# SY8003ADFC_4.net
KiCad netlist of a schematic drawn in Altium Designer
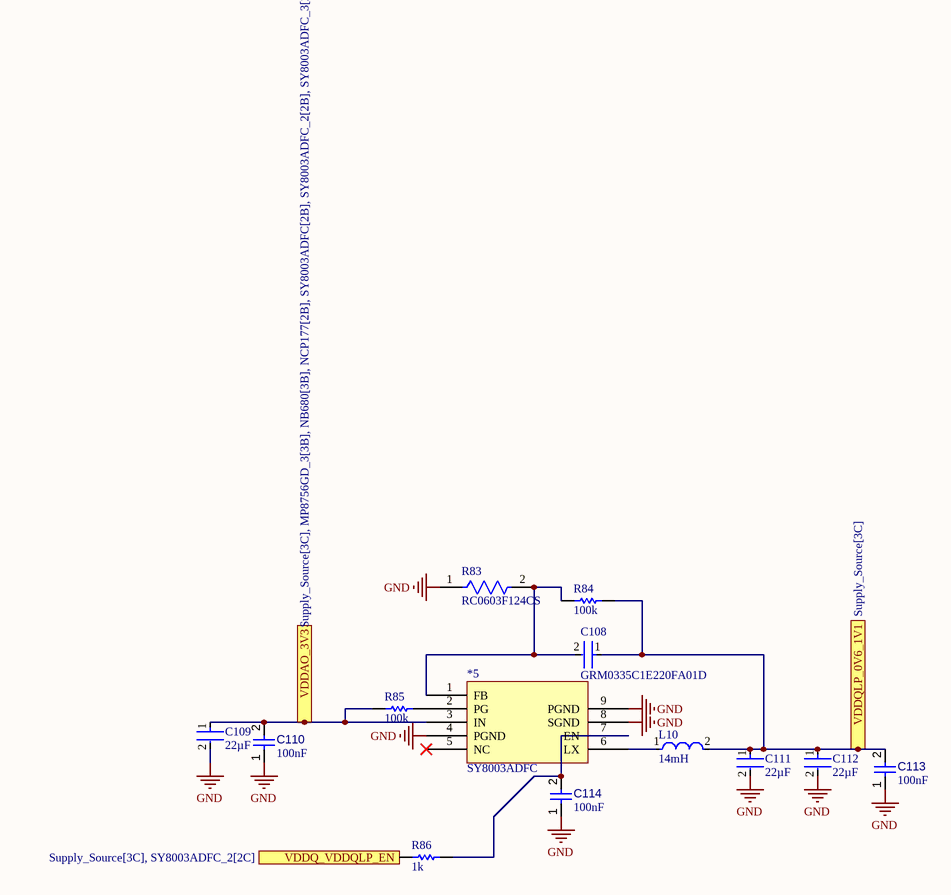
[diagram p0: SY8003ADFC_4.SchDoc]

(export (version "E")
  (design (tool "Eeschema 10.0.6"))
  (components
    (comp (ref "*5")
      (value "SY8003ADFC")
      (footprint "SON127P750X265-8N")
      (description "Switching Regulator, 3A, 1200kHz Switching Freq-Max, PDSO8")
      (libsource (lib "MIGUEL ANGEL ALVAREZ GUZMAN") (part "SY8003ADFC-Symbol-1"))
    )
    (comp (ref "C108")
      (value "GRM0335C1E220FA01D")
      (footprint "FP-GRM033-0_03-IPC_C")
      (description "Chip Multilayer Ceramic Capacitors for General Purpose, 0201, 22pF, C0G, 30ppm/°C, 1%, 25V")
      (fields (field (name "TOLERANCE") "1%"))
      (libsource (lib "Altium Content Vault") (part "b4654b650e69147ec39a6b967a45e02"))
    )
    (comp (ref "C109")
      (value "22µF")
      (footprint "FP-GRM186-0_2-IPC_A")
      (description "6.3V 22uF X5R ±20% 0603 Multilayer Ceramic Capacitors MLCC - SMD/SMT ROHS")
      (fields (field (name "TOLERANCE") "20%") (field (name "Comment") "GRM186R60J226ME15D"))
      (libsource (lib "MIGUEL ANGEL ALVAREZ GUZMAN") (part "02cd4be3c70576c341d710602a673aa"))
    )
    (comp (ref "C110")
      (value "100nF")
      (footprint "CAPC1005X56X25LL10T15")
      (description "Chip Capacitor, 0.1 uF, +/- 5%, 16 V, 0402 (1005 Metric)")
      (fields (field (name "TOLERANCE") "5%") (field (name "Comment") "Capacitor 0.1 uF +/- 5% 16 V 0402"))
      (libsource (lib "MIGUEL ANGEL ALVAREZ GUZMAN") (part "CAP-NP-2"))
    )
    (comp (ref "C111")
      (value "22µF")
      (footprint "FP-GRM186-0_2-IPC_A")
      (description "6.3V 22uF X5R ±20% 0603 Multilayer Ceramic Capacitors MLCC - SMD/SMT ROHS")
      (fields (field (name "TOLERANCE") "20%") (field (name "Comment") "GRM186R60J226ME15D"))
      (libsource (lib "MIGUEL ANGEL ALVAREZ GUZMAN") (part "02cd4be3c70576c341d710602a673aa"))
    )
    (comp (ref "C112")
      (value "22µF")
      (footprint "FP-GRM186-0_2-IPC_A")
      (description "6.3V 22uF X5R ±20% 0603 Multilayer Ceramic Capacitors MLCC - SMD/SMT ROHS")
      (fields (field (name "TOLERANCE") "20%") (field (name "Comment") "GRM186R60J226ME15D"))
      (libsource (lib "MIGUEL ANGEL ALVAREZ GUZMAN") (part "02cd4be3c70576c341d710602a673aa"))
    )
    (comp (ref "C113")
      (value "100nF")
      (footprint "CAPC1005X56X25LL10T15")
      (description "Chip Capacitor, 0.1 uF, +/- 5%, 16 V, 0402 (1005 Metric)")
      (fields (field (name "TOLERANCE") "5%") (field (name "Comment") "Capacitor 0.1 uF +/- 5% 16 V 0402"))
      (libsource (lib "MIGUEL ANGEL ALVAREZ GUZMAN") (part "CAP-NP-2"))
    )
    (comp (ref "C114")
      (value "100nF")
      (footprint "CAPC1005X56X25LL10T15")
      (description "Chip Capacitor, 0.1 uF, +/- 5%, 16 V, 0402 (1005 Metric)")
      (fields (field (name "TOLERANCE") "5%") (field (name "Comment") "Capacitor 0.1 uF +/- 5% 16 V 0402"))
      (libsource (lib "MIGUEL ANGEL ALVAREZ GUZMAN") (part "CAP-NP-2"))
    )
    (comp (ref "L10")
      (value "14mH")
      (footprint "FP-IHLP-2525CZ-FP_2_413x3-MFG")
      (description "Inductor High Current Shielded Wirewound 1.5uH 20% 100KHz 9A 15mOhm DCR 2525 T/R")
      (fields (field (name "TOLERANCE") "20%") (field (name "Comment") "IHLP2525CZER1R5M01"))
      (libsource (lib "MIGUEL ANGEL ALVAREZ GUZMAN") (part "725321dda6339637d4d059423bc1c3c"))
    )
    (comp (ref "R83")
      (value "RC0603F124CS")
      (footprint "FP-RC0603-MFG")
      (description "Res Thick Film 0201 120kΩ 1% 0.05W ±250ppm/°C Molded SMD T/R")
      (fields (field (name "TOLERANCE") "1%"))
      (libsource (lib "Altium Content Vault") (part "1029c3af85768c4190bb7ad29bc67b5"))
    )
    (comp (ref "R84")
      (value "100k")
      (footprint "RESC0603X26X15NL03T05")
      (description "Res General Purpose Thick Film 0201 100k Ohm 1% 1/20W ±200ppm/°C Molded Paper T/R")
      (fields (field (name "TOLERANCE") "1%") (field (name "Comment") "CRG0201F100K"))
      (libsource (lib "MIGUEL ANGEL ALVAREZ GUZMAN") (part "RES"))
    )
    (comp (ref "R85")
      (value "100k")
      (footprint "RESC0603X26X15NL03T05")
      (description "Res General Purpose Thick Film 0201 100k Ohm 1% 1/20W ±200ppm/°C Molded Paper T/R")
      (fields (field (name "TOLERANCE") "1%") (field (name "Comment") "CRG0201F100K"))
      (libsource (lib "MIGUEL ANGEL ALVAREZ GUZMAN") (part "RES"))
    )
    (comp (ref "R86")
      (value "1k")
      (footprint "RESC0603X26X15NL03T05")
      (description "Res General Purpose Thick Film 0201 1k Ohm 1% 1/20W ±200ppm/°C Molded Paper T/R")
      (fields (field (name "TOLERANCE") "1%") (field (name "Comment") "MCRE000140"))
      (libsource (lib "MIGUEL ANGEL ALVAREZ GUZMAN") (part "RES"))
    )
  )
  (nets
    (net (code "1") (name "/VDDAO_3V3") (class "Default")
      (node (ref "*5") (pin "3") (pinfunction "IN_3") (pintype "passive"))
      (node (ref "C109") (pin "1") (pinfunction "1_1") (pintype "passive"))
      (node (ref "C110") (pin "2") (pinfunction "2_2") (pintype "passive"))
      (node (ref "R85") (pin "1") (pinfunction "1_1") (pintype "passive"))
    )
    (net (code "2") (name "/VDDQLP_0V6_1V1") (class "Default")
      (node (ref "C108") (pin "1") (pinfunction "1_1") (pintype "passive"))
      (node (ref "C111") (pin "1") (pinfunction "1_1") (pintype "passive"))
      (node (ref "C112") (pin "1") (pinfunction "1_1") (pintype "passive"))
      (node (ref "C113") (pin "2") (pinfunction "2_2") (pintype "passive"))
      (node (ref "L10") (pin "2") (pinfunction "2_2") (pintype "passive"))
      (node (ref "R84") (pin "2") (pinfunction "2_2") (pintype "passive"))
    )
    (net (code "3") (name "/VDDQ_VDDQLP_EN") (class "Default")
      (node (ref "R86") (pin "1") (pinfunction "1_1") (pintype "passive"))
    )
    (net (code "4") (name "GND") (class "Default")
      (node (ref "*5") (pin "4") (pinfunction "PGND_4") (pintype "passive"))
      (node (ref "*5") (pin "8") (pinfunction "SGND_8") (pintype "passive"))
      (node (ref "*5") (pin "9") (pinfunction "PGND_9") (pintype "passive"))
      (node (ref "C109") (pin "2") (pinfunction "2_2") (pintype "passive"))
      (node (ref "C110") (pin "1") (pinfunction "1_1") (pintype "passive"))
      (node (ref "C111") (pin "2") (pinfunction "2_2") (pintype "passive"))
      (node (ref "C112") (pin "2") (pinfunction "2_2") (pintype "passive"))
      (node (ref "C113") (pin "1") (pinfunction "1_1") (pintype "passive"))
      (node (ref "C114") (pin "1") (pinfunction "1_1") (pintype "passive"))
      (node (ref "R83") (pin "1") (pinfunction "1_1") (pintype "passive"))
    )
    (net (code "5") (name "Net-(*5-EN)") (class "Default")
      (node (ref "*5") (pin "7") (pinfunction "EN_7") (pintype "passive"))
      (node (ref "C114") (pin "2") (pinfunction "2_2") (pintype "passive"))
      (node (ref "R86") (pin "2") (pinfunction "2_2") (pintype "passive"))
    )
    (net (code "6") (name "Net-(*5-FB)") (class "Default")
      (node (ref "*5") (pin "1") (pinfunction "FB_1") (pintype "passive"))
      (node (ref "C108") (pin "2") (pinfunction "2_2") (pintype "passive"))
      (node (ref "R83") (pin "2") (pinfunction "2_2") (pintype "passive"))
      (node (ref "R84") (pin "1") (pinfunction "1_1") (pintype "passive"))
    )
    (net (code "7") (name "Net-(*5-LX)") (class "Default")
      (node (ref "*5") (pin "6") (pinfunction "LX_6") (pintype "passive"))
      (node (ref "L10") (pin "1") (pinfunction "1_1") (pintype "passive"))
    )
    (net (code "8") (name "Net-(*5-PG)") (class "Default")
      (node (ref "*5") (pin "2") (pinfunction "PG_2") (pintype "passive"))
      (node (ref "R85") (pin "2") (pinfunction "2_2") (pintype "passive"))
    )
    (net (code "9") (name "unconnected-(*5-NC-Pad5)") (class "Default")
      (node (ref "*5") (pin "5") (pinfunction "NC_5") (pintype "passive+no_connect"))
    )
  )
)
